# MCU.net
KiCad netlist of a schematic drawn in Altium Designer
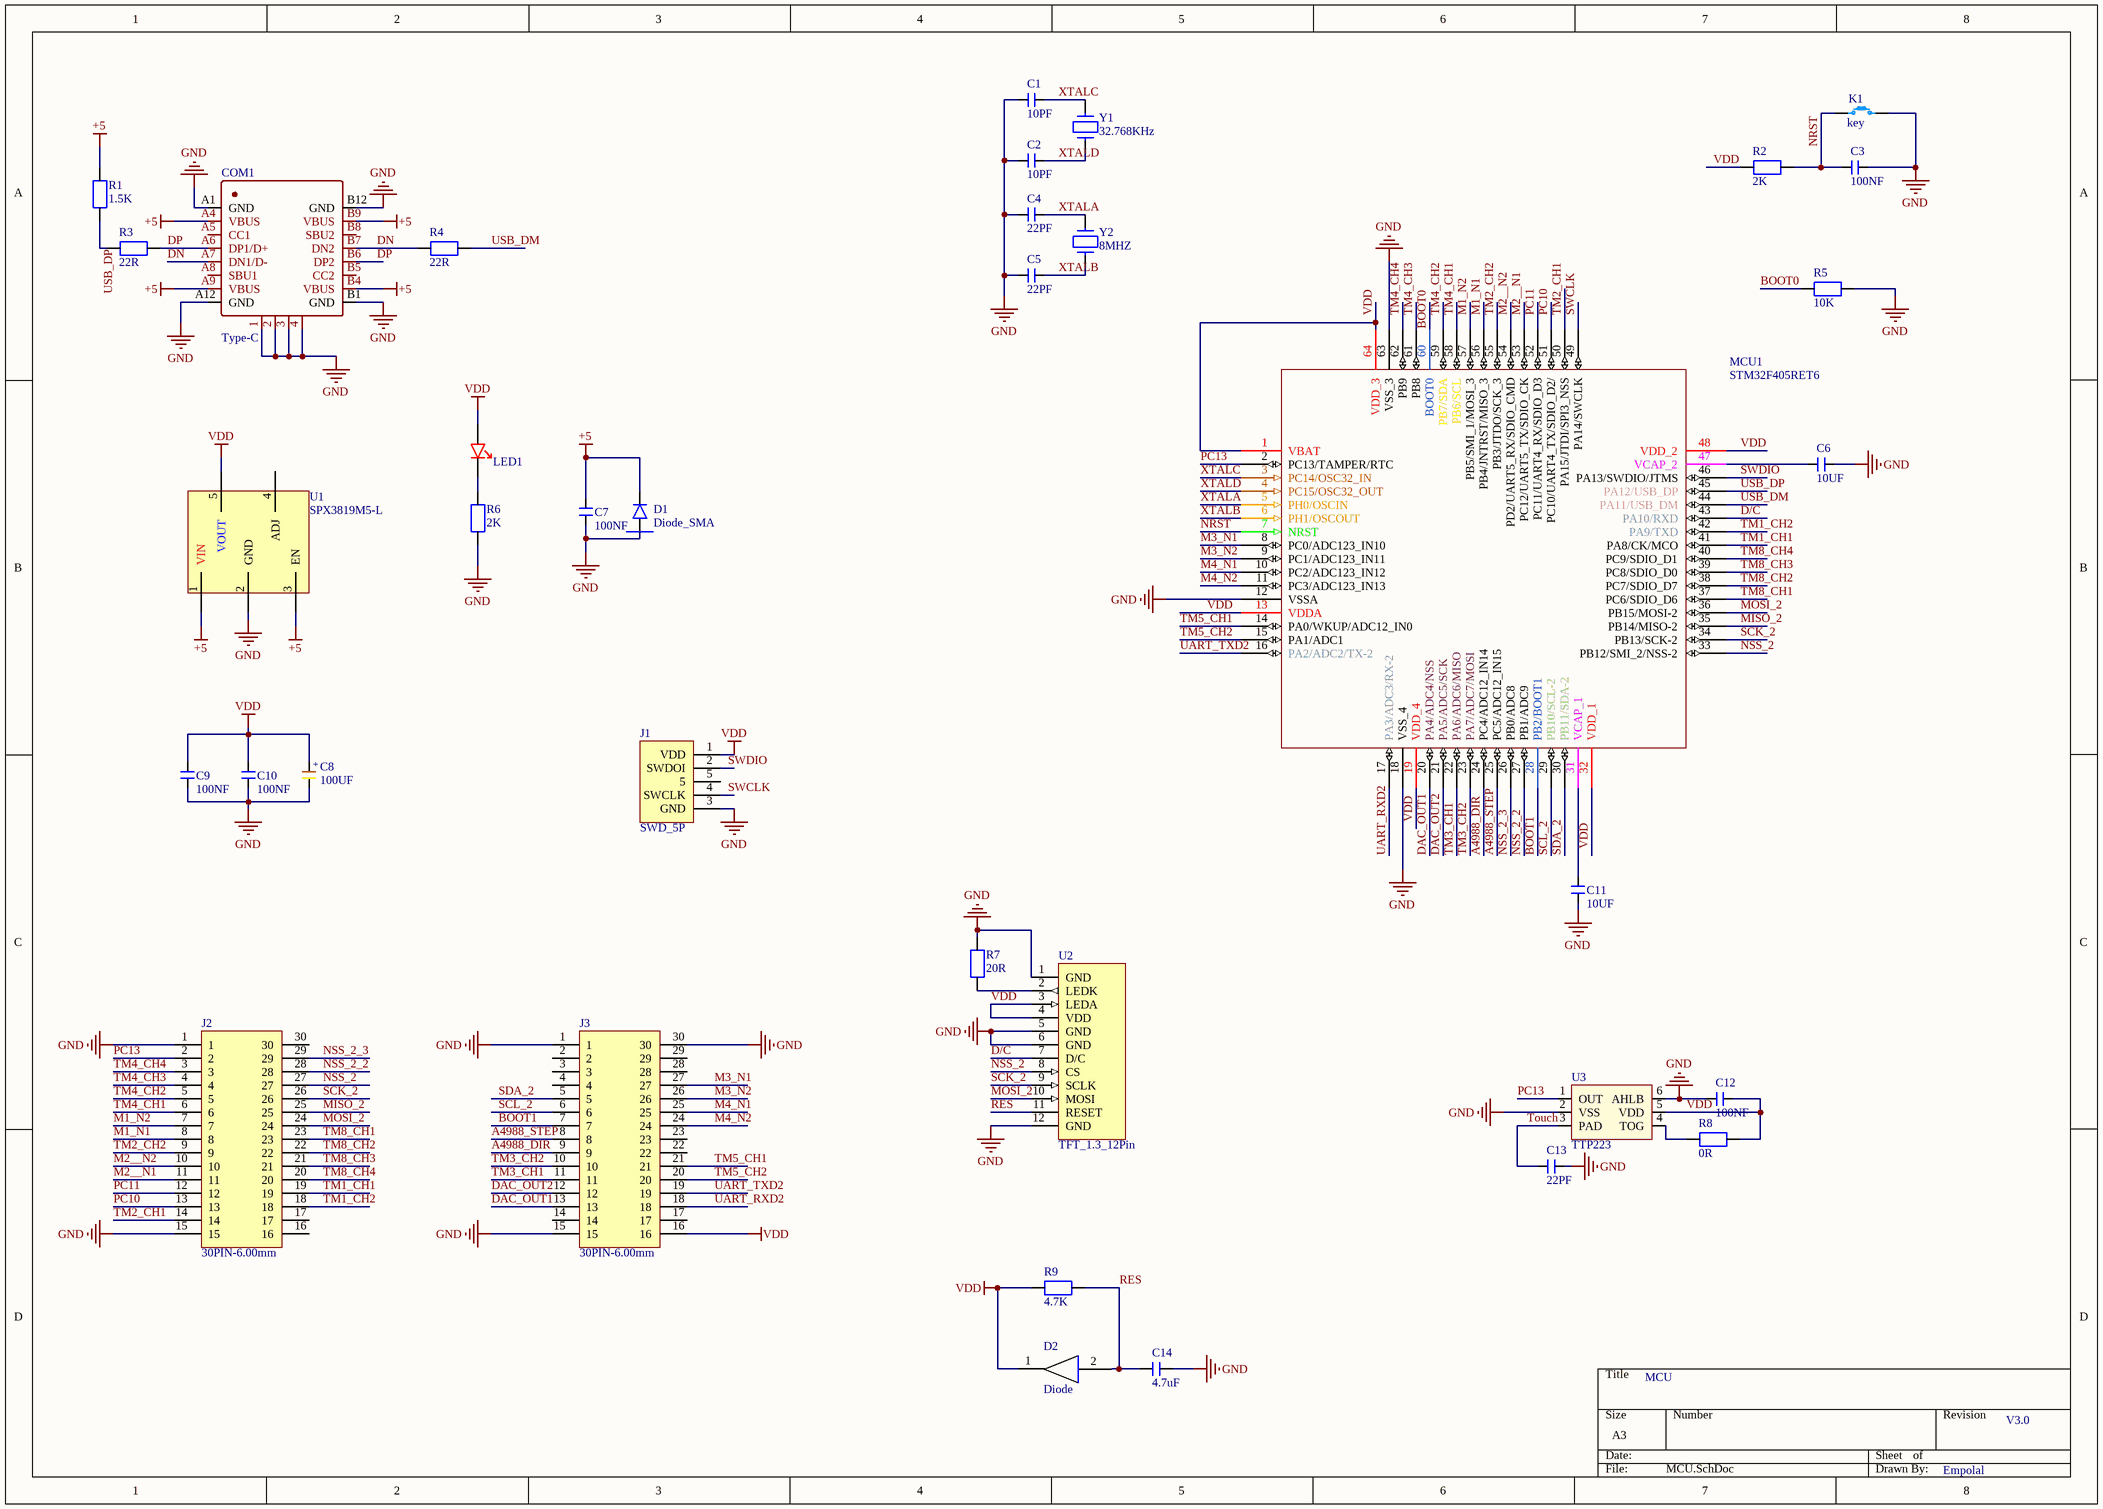
[diagram p0: MCU.SchDoc]

(export (version "E")
  (design (tool "Eeschema 10.0.6"))
  (components
    (comp (ref "C1")
      (value "10PF")
      (footprint "CAP_0603")
      (description "CAP  12~50V")
      (libsource (lib "Cavendish") (part "CAP"))
    )
    (comp (ref "C2")
      (value "10PF")
      (footprint "CAP_0603")
      (description "CAP  12~50V")
      (libsource (lib "Cavendish") (part "CAP"))
    )
    (comp (ref "C3")
      (value "100NF")
      (footprint "CAP_0603")
      (description "CAP  12~50V")
      (libsource (lib "Cavendish") (part "CAP"))
    )
    (comp (ref "C4")
      (value "22PF")
      (footprint "CAP_0603")
      (description "CAP  12~50V")
      (libsource (lib "Cavendish") (part "CAP"))
    )
    (comp (ref "C5")
      (value "22PF")
      (footprint "CAP_0603")
      (description "CAP  12~50V")
      (libsource (lib "Cavendish") (part "CAP"))
    )
    (comp (ref "C6")
      (value "10UF")
      (footprint "CAP_0603")
      (description "CAP  12~50V")
      (libsource (lib "Cavendish") (part "CAP"))
    )
    (comp (ref "C7")
      (value "100NF")
      (footprint "CAP_0603")
      (description "CAP  12~50V")
      (libsource (lib "Cavendish") (part "CAP"))
    )
    (comp (ref "C8")
      (value "100UF")
      (footprint "CAP_3528_B")
      (description "CAP  6~12V  钽电容")
      (libsource (lib "Cavendish") (part "CAP_TA"))
    )
    (comp (ref "C9")
      (value "100NF")
      (footprint "CAP_0603")
      (description "CAP  12~50V")
      (libsource (lib "Cavendish") (part "CAP"))
    )
    (comp (ref "C10")
      (value "100NF")
      (footprint "CAP_0603")
      (description "CAP  12~50V")
      (libsource (lib "Cavendish") (part "CAP"))
    )
    (comp (ref "C11")
      (value "10UF")
      (footprint "CAP_0603")
      (description "CAP  12~50V")
      (libsource (lib "Cavendish") (part "CAP"))
    )
    (comp (ref "C12")
      (value "100NF")
      (footprint "CAP_0603")
      (description "CAP  12~50V")
      (libsource (lib "Cavendish") (part "CAP"))
    )
    (comp (ref "C13")
      (value "22PF")
      (footprint "CAP_0603")
      (description "CAP  12~50V")
      (libsource (lib "Cavendish") (part "CAP"))
    )
    (comp (ref "C14")
      (value "4.7uF")
      (footprint "CAP_0603")
      (description "CAP")
      (libsource (lib "Cavendish") (part "CAP_SDM"))
    )
    (comp (ref "COM1")
      (value "Type-C")
      (footprint "USB-tYPE_C_C")
      (description "USB")
      (libsource (lib "MCU") (part "USB-type_c"))
    )
    (comp (ref "D1")
      (value "Diode_SMA")
      (footprint "DIODE_SOD123")
      (description "Diode_肖特基")
      (libsource (lib "Cavendish") (part "Diode-SM"))
    )
    (comp (ref "D2")
      (value "Diode")
      (footprint "SOD123")
      (description "开关二极管")
      (libsource (lib "Cavendish") (part "Diode-SOD"))
    )
    (comp (ref "J1")
      (value "SWD_5P")
      (footprint "XH2.54-WS-5P")
      (description "线对线连接器")
      (libsource (lib "MCU") (part "SWD_5P"))
    )
    (comp (ref "J2")
      (value "30PIN-6.00mm")
      (footprint "BTB_Double_30Pin_Up")
      (libsource (lib "Cavendish") (part "BTB_DOUBLE_30PIN"))
    )
    (comp (ref "J3")
      (value "30PIN-6.00mm")
      (footprint "BTB_Double_30Pin_Up")
      (libsource (lib "Cavendish") (part "BTB_DOUBLE_30PIN"))
    )
    (comp (ref "K1")
      (value "key")
      (footprint "KEY-A")
      (description "Key")
      (libsource (lib "Cavendish") (part "key"))
    )
    (comp (ref "LED1")
      (value "LED_R/G/B/Y")
      (footprint "RGB_3528")
      (description "LED")
      (libsource (lib "Cavendish") (part "LED"))
    )
    (comp (ref "MCU1")
      (value "STM32F405RET6")
      (footprint "LQFP_64_10X10")
      (description "MCU")
      (libsource (lib "Cavendish") (part "STM32f4_R"))
    )
    (comp (ref "R1")
      (value "1.5K")
      (footprint "RESC_0603_2")
      (description "RES 贴片")
      (libsource (lib "Cavendish") (part "RES_S"))
    )
    (comp (ref "R2")
      (value "2K")
      (footprint "RESC_0603_2")
      (description "RES 贴片")
      (libsource (lib "Cavendish") (part "RES_S"))
    )
    (comp (ref "R3")
      (value "22R")
      (footprint "RESC_0603_2")
      (description "RES 贴片")
      (libsource (lib "Cavendish") (part "RES_S"))
    )
    (comp (ref "R4")
      (value "22R")
      (footprint "RESC_0603_2")
      (description "RES 贴片")
      (libsource (lib "Cavendish") (part "RES_S"))
    )
    (comp (ref "R5")
      (value "10K")
      (footprint "RESC_0603_2")
      (description "RES 贴片")
      (libsource (lib "Cavendish") (part "RES_S"))
    )
    (comp (ref "R6")
      (value "2K")
      (footprint "RESC_0603_2")
      (description "RES 贴片")
      (libsource (lib "Cavendish") (part "RES_S"))
    )
    (comp (ref "R7")
      (value "20R")
      (footprint "RESC_0603_2")
      (description "RES 贴片")
      (libsource (lib "Cavendish") (part "RES_S"))
    )
    (comp (ref "R8")
      (value "0R")
      (footprint "RESC_0603_2")
      (description "RES 贴片")
      (libsource (lib "Cavendish") (part "RES_S"))
    )
    (comp (ref "R9")
      (value "4.7K")
      (footprint "RESC_0603_2")
      (description "RES 贴片")
      (libsource (lib "Cavendish") (part "RES_S"))
    )
    (comp (ref "U1")
      (value "SPX3819M5-L")
      (footprint "SOT23_5")
      (description "DC-DC   3.3V  500ma")
      (libsource (lib "Cavendish") (part "SPX3819M5-L"))
    )
    (comp (ref "U2")
      (value "TFT_1.3_12Pin")
      (footprint "LCD_1.3B")
      (description "ST7789V-SPI")
      (libsource (lib "Cavendish") (part "LCD_1.3   T"))
    )
    (comp (ref "U3")
      (value "TTP223")
      (footprint "SOT-23-6")
      (description "触摸芯片")
      (libsource (lib "Cavendish") (part "TTP223"))
    )
    (comp (ref "Y1")
      (value "32.768KHz")
      (footprint "XTAL_SMD_3215")
      (description "CRYSTAL")
      (libsource (lib "Cavendish") (part "XTAL"))
    )
    (comp (ref "Y2")
      (value "8MHZ")
      (footprint "XTAL_3225")
      (description "CRYSTAL")
      (libsource (lib "Cavendish") (part "XTAL"))
    )
  )
  (nets
    (net (code "1") (name "+5") (class "Default")
      (node (ref "C7") (pin "2") (pinfunction "0_2") (pintype "passive"))
      (node (ref "COM1") (pin "A4") (pinfunction "VBUS_A4") (pintype "passive"))
      (node (ref "COM1") (pin "A9") (pinfunction "VBUS_A9") (pintype "passive"))
      (node (ref "COM1") (pin "B4") (pinfunction "VBUS_B4") (pintype "passive"))
      (node (ref "COM1") (pin "B9") (pinfunction "VBUS_B9") (pintype "passive"))
      (node (ref "D1") (pin "2") (pinfunction "N_2") (pintype "passive"))
      (node (ref "R1") (pin "2") (pinfunction "2_2") (pintype "passive"))
      (node (ref "U1") (pin "1") (pinfunction "VIN_1") (pintype "passive"))
      (node (ref "U1") (pin "3") (pinfunction "EN_3") (pintype "passive"))
    )
    (net (code "2") (name "/A4988_DIR") (class "Default")
      (node (ref "J3") (pin "9") (pinfunction "9_9") (pintype "passive"))
      (node (ref "MCU1") (pin "24") (pinfunction "PC4/ADC12_IN14_24") (pintype "bidirectional"))
    )
    (net (code "3") (name "/A4988_STEP") (class "Default")
      (node (ref "J3") (pin "8") (pinfunction "8_8") (pintype "passive"))
      (node (ref "MCU1") (pin "25") (pinfunction "PC5/ADC12_IN15_25") (pintype "bidirectional"))
    )
    (net (code "4") (name "/BOOT0") (class "Default")
      (node (ref "MCU1") (pin "60") (pinfunction "BOOT0_60") (pintype "passive"))
      (node (ref "R5") (pin "1") (pinfunction "1_1") (pintype "passive"))
    )
    (net (code "5") (name "/BOOT1") (class "Default")
      (node (ref "J3") (pin "7") (pinfunction "7_7") (pintype "passive"))
      (node (ref "MCU1") (pin "28") (pinfunction "PB2/BOOT1_28") (pintype "passive"))
    )
    (net (code "6") (name "/DAC_OUT1") (class "Default")
      (node (ref "J3") (pin "13") (pinfunction "13_13") (pintype "passive"))
      (node (ref "MCU1") (pin "20") (pinfunction "PA4/ADC4/NSS_20") (pintype "bidirectional"))
    )
    (net (code "7") (name "/DAC_OUT2") (class "Default")
      (node (ref "J3") (pin "12") (pinfunction "12_12") (pintype "passive"))
      (node (ref "MCU1") (pin "21") (pinfunction "PA5/ADC5/SCK_21") (pintype "bidirectional"))
    )
    (net (code "8") (name "/DN") (class "Default")
      (node (ref "COM1") (pin "A7") (pinfunction "DN1/D-_A7") (pintype "passive"))
      (node (ref "COM1") (pin "B7") (pinfunction "DN2_B7") (pintype "passive"))
      (node (ref "R4") (pin "1") (pinfunction "1_1") (pintype "passive"))
    )
    (net (code "9") (name "/DP") (class "Default")
      (node (ref "COM1") (pin "A6") (pinfunction "DP1/D+_A6") (pintype "passive"))
      (node (ref "COM1") (pin "B6") (pinfunction "DP2_B6") (pintype "passive"))
      (node (ref "R3") (pin "2") (pinfunction "2_2") (pintype "passive"))
    )
    (net (code "10") (name "/D{slash}C") (class "Default")
      (node (ref "MCU1") (pin "43") (pinfunction "PA10/RXD_43") (pintype "bidirectional"))
      (node (ref "U2") (pin "7") (pinfunction "D/C_7") (pintype "passive"))
    )
    (net (code "11") (name "/M1_N1") (class "Default")
      (node (ref "J2") (pin "8") (pinfunction "8_8") (pintype "passive"))
      (node (ref "MCU1") (pin "56") (pinfunction "PB4/JNTRST/MISO_3_56") (pintype "bidirectional"))
    )
    (net (code "12") (name "/M1_N2") (class "Default")
      (node (ref "J2") (pin "7") (pinfunction "7_7") (pintype "passive"))
      (node (ref "MCU1") (pin "57") (pinfunction "PB5/SMI_1/MOSI_3_57") (pintype "bidirectional"))
    )
    (net (code "13") (name "/M2__N1") (class "Default")
      (node (ref "J2") (pin "11") (pinfunction "11_11") (pintype "passive"))
      (node (ref "MCU1") (pin "53") (pinfunction "PC12/UART5_TX/SDIO_CK_53") (pintype "bidirectional"))
    )
    (net (code "14") (name "/M2__N2") (class "Default")
      (node (ref "J2") (pin "10") (pinfunction "10_10") (pintype "passive"))
      (node (ref "MCU1") (pin "54") (pinfunction "PD2/UART5_RX/SDIO_CMD_54") (pintype "bidirectional"))
    )
    (net (code "15") (name "/M3_N1") (class "Default")
      (node (ref "J3") (pin "27") (pinfunction "27_27") (pintype "passive"))
      (node (ref "MCU1") (pin "8") (pinfunction "PC0/ADC123_IN10_8") (pintype "bidirectional"))
    )
    (net (code "16") (name "/M3_N2") (class "Default")
      (node (ref "J3") (pin "26") (pinfunction "26_26") (pintype "passive"))
      (node (ref "MCU1") (pin "9") (pinfunction "PC1/ADC123_IN11_9") (pintype "bidirectional"))
    )
    (net (code "17") (name "/M4_N1") (class "Default")
      (node (ref "J3") (pin "25") (pinfunction "25_25") (pintype "passive"))
      (node (ref "MCU1") (pin "10") (pinfunction "PC2/ADC123_IN12_10") (pintype "bidirectional"))
    )
    (net (code "18") (name "/M4_N2") (class "Default")
      (node (ref "J3") (pin "24") (pinfunction "24_24") (pintype "passive"))
      (node (ref "MCU1") (pin "11") (pinfunction "PC3/ADC123_IN13_11") (pintype "bidirectional"))
    )
    (net (code "19") (name "/MISO_2") (class "Default")
      (node (ref "J2") (pin "25") (pinfunction "25_25") (pintype "passive"))
      (node (ref "MCU1") (pin "35") (pinfunction "PB14/MISO-2_35") (pintype "bidirectional"))
    )
    (net (code "20") (name "/MOSI_2") (class "Default")
      (node (ref "J2") (pin "24") (pinfunction "24_24") (pintype "passive"))
      (node (ref "MCU1") (pin "36") (pinfunction "PB15/MOSI-2_36") (pintype "bidirectional"))
      (node (ref "U2") (pin "10") (pinfunction "MOSI_10") (pintype "input"))
    )
    (net (code "21") (name "/NRST") (class "Default")
      (node (ref "C3") (pin "1") (pinfunction "0_1") (pintype "passive"))
      (node (ref "K1") (pin "2") (pintype "passive"))
      (node (ref "MCU1") (pin "7") (pinfunction "NRST_7") (pintype "input"))
      (node (ref "R2") (pin "2") (pinfunction "2_2") (pintype "passive"))
    )
    (net (code "22") (name "/NSS_2") (class "Default")
      (node (ref "J2") (pin "27") (pinfunction "27_27") (pintype "passive"))
      (node (ref "MCU1") (pin "33") (pinfunction "PB12/SMI_2/NSS-2_33") (pintype "bidirectional"))
      (node (ref "U2") (pin "8") (pinfunction "CS_8") (pintype "input"))
    )
    (net (code "23") (name "/NSS_2_2") (class "Default")
      (node (ref "J2") (pin "28") (pinfunction "28_28") (pintype "passive"))
      (node (ref "MCU1") (pin "27") (pinfunction "PB1/ADC9_27") (pintype "bidirectional"))
    )
    (net (code "24") (name "/NSS_2_3") (class "Default")
      (node (ref "J2") (pin "29") (pinfunction "29_29") (pintype "passive"))
      (node (ref "MCU1") (pin "26") (pinfunction "PB0/ADC8_26") (pintype "bidirectional"))
    )
    (net (code "25") (name "/PC10") (class "Default")
      (node (ref "J2") (pin "13") (pinfunction "13_13") (pintype "passive"))
      (node (ref "MCU1") (pin "51") (pinfunction "PC10/UART4_TX/SDIO_D2/_51") (pintype "bidirectional"))
    )
    (net (code "26") (name "/PC11") (class "Default")
      (node (ref "J2") (pin "12") (pinfunction "12_12") (pintype "passive"))
      (node (ref "MCU1") (pin "52") (pinfunction "PC11/UART4_RX/SDIO_D3_52") (pintype "bidirectional"))
    )
    (net (code "27") (name "/PC13") (class "Default")
      (node (ref "J2") (pin "2") (pinfunction "2_2") (pintype "passive"))
      (node (ref "MCU1") (pin "2") (pinfunction "PC13/TAMPER/RTC_2") (pintype "bidirectional"))
      (node (ref "U3") (pin "1") (pinfunction "OUT_1") (pintype "passive"))
    )
    (net (code "28") (name "/RES") (class "Default")
      (node (ref "C14") (pin "1") (pinfunction "0_1") (pintype "passive"))
      (node (ref "D2") (pin "2") (pinfunction "P_2") (pintype "passive"))
      (node (ref "R9") (pin "2") (pinfunction "2_2") (pintype "passive"))
      (node (ref "U2") (pin "11") (pinfunction "RESET_11") (pintype "passive"))
    )
    (net (code "29") (name "/SCK_2") (class "Default")
      (node (ref "J2") (pin "26") (pinfunction "26_26") (pintype "passive"))
      (node (ref "MCU1") (pin "34") (pinfunction "PB13/SCK-2_34") (pintype "bidirectional"))
      (node (ref "U2") (pin "9") (pinfunction "SCLK_9") (pintype "input"))
    )
    (net (code "30") (name "/SCL_2") (class "Default")
      (node (ref "J3") (pin "6") (pinfunction "6_6") (pintype "passive"))
      (node (ref "MCU1") (pin "29") (pinfunction "PB10/SCL-2_29") (pintype "bidirectional"))
    )
    (net (code "31") (name "/SDA_2") (class "Default")
      (node (ref "J3") (pin "5") (pinfunction "5_5") (pintype "passive"))
      (node (ref "MCU1") (pin "30") (pinfunction "PB11/SDA-2_30") (pintype "bidirectional"))
    )
    (net (code "32") (name "/SWCLK") (class "Default")
      (node (ref "J1") (pin "4") (pinfunction "SWCLK_4") (pintype "passive"))
      (node (ref "MCU1") (pin "49") (pinfunction "PA14/SWCLK_49") (pintype "bidirectional"))
    )
    (net (code "33") (name "/SWDIO") (class "Default")
      (node (ref "J1") (pin "2") (pinfunction "SWDOI_2") (pintype "passive"))
      (node (ref "MCU1") (pin "46") (pinfunction "PA13/SWDIO/JTMS_46") (pintype "bidirectional"))
    )
    (net (code "34") (name "/TM1_CH1") (class "Default")
      (node (ref "J2") (pin "19") (pinfunction "19_19") (pintype "passive"))
      (node (ref "MCU1") (pin "41") (pinfunction "PA8/CK/MCO_41") (pintype "bidirectional"))
    )
    (net (code "35") (name "/TM1_CH2") (class "Default")
      (node (ref "J2") (pin "18") (pinfunction "18_18") (pintype "passive"))
      (node (ref "MCU1") (pin "42") (pinfunction "PA9/TXD_42") (pintype "bidirectional"))
    )
    (net (code "36") (name "/TM2_CH1") (class "Default")
      (node (ref "J2") (pin "14") (pinfunction "14_14") (pintype "passive"))
      (node (ref "MCU1") (pin "50") (pinfunction "PA15/JTDI/SPI3_NSS_50") (pintype "bidirectional"))
    )
    (net (code "37") (name "/TM2_CH2") (class "Default")
      (node (ref "J2") (pin "9") (pinfunction "9_9") (pintype "passive"))
      (node (ref "MCU1") (pin "55") (pinfunction "PB3/JTDO/SCK_3_55") (pintype "bidirectional"))
    )
    (net (code "38") (name "/TM3_CH1") (class "Default")
      (node (ref "J3") (pin "11") (pinfunction "11_11") (pintype "passive"))
      (node (ref "MCU1") (pin "22") (pinfunction "PA6/ADC6/MISO_22") (pintype "bidirectional"))
    )
    (net (code "39") (name "/TM3_CH2") (class "Default")
      (node (ref "J3") (pin "10") (pinfunction "10_10") (pintype "passive"))
      (node (ref "MCU1") (pin "23") (pinfunction "PA7/ADC7/MOSI_23") (pintype "bidirectional"))
    )
    (net (code "40") (name "/TM4_CH1") (class "Default")
      (node (ref "J2") (pin "6") (pinfunction "6_6") (pintype "passive"))
      (node (ref "MCU1") (pin "58") (pinfunction "PB6/SCL_58") (pintype "bidirectional"))
    )
    (net (code "41") (name "/TM4_CH2") (class "Default")
      (node (ref "J2") (pin "5") (pinfunction "5_5") (pintype "passive"))
      (node (ref "MCU1") (pin "59") (pinfunction "PB7/SDA_59") (pintype "bidirectional"))
    )
    (net (code "42") (name "/TM4_CH3") (class "Default")
      (node (ref "J2") (pin "4") (pinfunction "4_4") (pintype "passive"))
      (node (ref "MCU1") (pin "61") (pinfunction "PB8_61") (pintype "bidirectional"))
    )
    (net (code "43") (name "/TM4_CH4") (class "Default")
      (node (ref "J2") (pin "3") (pinfunction "3_3") (pintype "passive"))
      (node (ref "MCU1") (pin "62") (pinfunction "PB9_62") (pintype "bidirectional"))
    )
    (net (code "44") (name "/TM5_CH1") (class "Default")
      (node (ref "J3") (pin "21") (pinfunction "21_21") (pintype "passive"))
      (node (ref "MCU1") (pin "14") (pinfunction "PA0/WKUP/ADC12_IN0_14") (pintype "bidirectional"))
    )
    (net (code "45") (name "/TM5_CH2") (class "Default")
      (node (ref "J3") (pin "20") (pinfunction "20_20") (pintype "passive"))
      (node (ref "MCU1") (pin "15") (pinfunction "PA1/ADC1_15") (pintype "bidirectional"))
    )
    (net (code "46") (name "/TM8_CH1") (class "Default")
      (node (ref "J2") (pin "23") (pinfunction "23_23") (pintype "passive"))
      (node (ref "MCU1") (pin "37") (pinfunction "PC6/SDIO_D6_37") (pintype "bidirectional"))
    )
    (net (code "47") (name "/TM8_CH2") (class "Default")
      (node (ref "J2") (pin "22") (pinfunction "22_22") (pintype "passive"))
      (node (ref "MCU1") (pin "38") (pinfunction "PC7/SDIO_D7_38") (pintype "bidirectional"))
    )
    (net (code "48") (name "/TM8_CH3") (class "Default")
      (node (ref "J2") (pin "21") (pinfunction "21_21") (pintype "passive"))
      (node (ref "MCU1") (pin "39") (pinfunction "PC8/SDIO_D0_39") (pintype "bidirectional"))
    )
    (net (code "49") (name "/TM8_CH4") (class "Default")
      (node (ref "J2") (pin "20") (pinfunction "20_20") (pintype "passive"))
      (node (ref "MCU1") (pin "40") (pinfunction "PC9/SDIO_D1_40") (pintype "bidirectional"))
    )
    (net (code "50") (name "/Touch") (class "Default")
      (node (ref "C13") (pin "1") (pinfunction "0_1") (pintype "passive"))
      (node (ref "U3") (pin "3") (pinfunction "PAD_3") (pintype "passive"))
    )
    (net (code "51") (name "/UART_RXD2") (class "Default")
      (node (ref "J3") (pin "18") (pinfunction "18_18") (pintype "passive"))
      (node (ref "MCU1") (pin "17") (pinfunction "PA3/ADC3/RX-2_17") (pintype "bidirectional"))
    )
    (net (code "52") (name "/UART_TXD2") (class "Default")
      (node (ref "J3") (pin "19") (pinfunction "19_19") (pintype "passive"))
      (node (ref "MCU1") (pin "16") (pinfunction "PA2/ADC2/TX-2_16") (pintype "bidirectional"))
    )
    (net (code "53") (name "/USB_DM") (class "Default")
      (node (ref "MCU1") (pin "44") (pinfunction "PA11/USB_DM_44") (pintype "bidirectional"))
      (node (ref "R4") (pin "2") (pinfunction "2_2") (pintype "passive"))
    )
    (net (code "54") (name "/USB_DP") (class "Default")
      (node (ref "MCU1") (pin "45") (pinfunction "PA12/USB_DP_45") (pintype "bidirectional"))
      (node (ref "R1") (pin "1") (pinfunction "1_1") (pintype "passive"))
      (node (ref "R3") (pin "1") (pinfunction "1_1") (pintype "passive"))
    )
    (net (code "55") (name "/XTALA") (class "Default")
      (node (ref "C4") (pin "2") (pinfunction "0_2") (pintype "passive"))
      (node (ref "MCU1") (pin "5") (pinfunction "PH0/OSCIN_5") (pintype "input"))
      (node (ref "Y2") (pin "2") (pinfunction "2_2") (pintype "passive"))
    )
    (net (code "56") (name "/XTALB") (class "Default")
      (node (ref "C5") (pin "2") (pinfunction "0_2") (pintype "passive"))
      (node (ref "MCU1") (pin "6") (pinfunction "PH1/OSCOUT_6") (pintype "input"))
      (node (ref "Y2") (pin "1") (pinfunction "1_1") (pintype "passive"))
    )
    (net (code "57") (name "/XTALC") (class "Default")
      (node (ref "C1") (pin "2") (pinfunction "0_2") (pintype "passive"))
      (node (ref "MCU1") (pin "3") (pinfunction "PC14/OSC32_IN_3") (pintype "input"))
      (node (ref "Y1") (pin "2") (pinfunction "2_2") (pintype "passive"))
    )
    (net (code "58") (name "/XTALD") (class "Default")
      (node (ref "C2") (pin "2") (pinfunction "0_2") (pintype "passive"))
      (node (ref "MCU1") (pin "4") (pinfunction "PC15/OSC32_OUT_4") (pintype "input"))
      (node (ref "Y1") (pin "1") (pinfunction "1_1") (pintype "passive"))
    )
    (net (code "59") (name "GND") (class "Default")
      (node (ref "C1") (pin "1") (pinfunction "0_1") (pintype "passive"))
      (node (ref "C10") (pin "1") (pinfunction "0_1") (pintype "passive"))
      (node (ref "C11") (pin "1") (pinfunction "0_1") (pintype "passive"))
      (node (ref "C12") (pin "1") (pinfunction "0_1") (pintype "passive"))
      (node (ref "C13") (pin "2") (pinfunction "0_2") (pintype "passive"))
      (node (ref "C14") (pin "2") (pinfunction "0_2") (pintype "passive"))
      (node (ref "C2") (pin "1") (pinfunction "0_1") (pintype "passive"))
      (node (ref "C3") (pin "2") (pinfunction "0_2") (pintype "passive"))
      (node (ref "C4") (pin "1") (pinfunction "0_1") (pintype "passive"))
      (node (ref "C5") (pin "1") (pinfunction "0_1") (pintype "passive"))
      (node (ref "C6") (pin "2") (pinfunction "0_2") (pintype "passive"))
      (node (ref "C7") (pin "1") (pinfunction "0_1") (pintype "passive"))
      (node (ref "C8") (pin "2") (pinfunction "0_2") (pintype "passive"))
      (node (ref "C9") (pin "1") (pinfunction "0_1") (pintype "passive"))
      (node (ref "COM1") (pin "1") (pinfunction "1_1") (pintype "passive"))
      (node (ref "COM1") (pin "2") (pinfunction "2_2") (pintype "passive"))
      (node (ref "COM1") (pin "3") (pinfunction "3_3") (pintype "passive"))
      (node (ref "COM1") (pin "4") (pinfunction "4_4") (pintype "passive"))
      (node (ref "COM1") (pin "A1") (pinfunction "GND_A1") (pintype "passive"))
      (node (ref "COM1") (pin "A12") (pinfunction "GND_A12") (pintype "passive"))
      (node (ref "COM1") (pin "B1") (pinfunction "GND_B1") (pintype "passive"))
      (node (ref "COM1") (pin "B12") (pinfunction "GND_B12") (pintype "passive"))
      (node (ref "D1") (pin "1") (pinfunction "P_1") (pintype "passive"))
      (node (ref "J1") (pin "3") (pinfunction "GND_3") (pintype "passive"))
      (node (ref "J2") (pin "1") (pinfunction "1_1") (pintype "passive"))
      (node (ref "J2") (pin "15") (pinfunction "15_15") (pintype "passive"))
      (node (ref "J3") (pin "1") (pinfunction "1_1") (pintype "passive"))
      (node (ref "J3") (pin "15") (pinfunction "15_15") (pintype "passive"))
      (node (ref "J3") (pin "30") (pinfunction "30_30") (pintype "passive"))
      (node (ref "K1") (pin "1") (pintype "passive"))
      (node (ref "MCU1") (pin "12") (pinfunction "VSSA_12") (pintype "power_in"))
      (node (ref "MCU1") (pin "18") (pinfunction "VSS_4_18") (pintype "power_in"))
      (node (ref "MCU1") (pin "63") (pinfunction "VSS_3_63") (pintype "power_in"))
      (node (ref "R5") (pin "2") (pinfunction "2_2") (pintype "passive"))
      (node (ref "R6") (pin "1") (pinfunction "1_1") (pintype "passive"))
      (node (ref "R7") (pin "2") (pinfunction "2_2") (pintype "passive"))
      (node (ref "U1") (pin "2") (pinfunction "GND_2") (pintype "passive"))
      (node (ref "U2") (pin "1") (pinfunction "GND_1") (pintype "passive"))
      (node (ref "U2") (pin "12") (pinfunction "GND_12") (pintype "passive"))
      (node (ref "U2") (pin "5") (pinfunction "GND_5") (pintype "passive"))
      (node (ref "U2") (pin "6") (pinfunction "GND_6") (pintype "passive"))
      (node (ref "U3") (pin "2") (pinfunction "VSS_2") (pintype "passive"))
      (node (ref "U3") (pin "6") (pinfunction "AHLB_6") (pintype "passive"))
    )
    (net (code "60") (name "Net-(LED1--)") (class "Default")
      (node (ref "LED1") (pin "1") (pinfunction "-_1") (pintype "passive"))
      (node (ref "R6") (pin "2") (pinfunction "2_2") (pintype "passive"))
    )
    (net (code "61") (name "Net-(MCU1-VCAP_1)") (class "Default")
      (node (ref "C11") (pin "2") (pinfunction "0_2") (pintype "passive"))
      (node (ref "MCU1") (pin "31") (pinfunction "VCAP_1_31") (pintype "passive"))
    )
    (net (code "62") (name "Net-(MCU1-VCAP_2)") (class "Default")
      (node (ref "C6") (pin "1") (pinfunction "0_1") (pintype "passive"))
      (node (ref "MCU1") (pin "47") (pinfunction "VCAP_2_47") (pintype "passive"))
    )
    (net (code "63") (name "Net-(U2-LEDK)") (class "Default")
      (node (ref "R7") (pin "1") (pinfunction "1_1") (pintype "passive"))
      (node (ref "U2") (pin "2") (pinfunction "LEDK_2") (pintype "output"))
    )
    (net (code "64") (name "Net-(U3-TOG)") (class "Default")
      (node (ref "R8") (pin "2") (pinfunction "2_2") (pintype "passive"))
      (node (ref "U3") (pin "4") (pinfunction "TOG_4") (pintype "passive"))
    )
    (net (code "65") (name "VDD") (class "Default")
      (node (ref "C10") (pin "2") (pinfunction "0_2") (pintype "passive"))
      (node (ref "C12") (pin "2") (pinfunction "0_2") (pintype "passive"))
      (node (ref "C8") (pin "1") (pinfunction "0_1") (pintype "passive"))
      (node (ref "C9") (pin "2") (pinfunction "0_2") (pintype "passive"))
      (node (ref "D2") (pin "1") (pinfunction "N_1") (pintype "passive"))
      (node (ref "J1") (pin "1") (pinfunction "VDD_1") (pintype "passive"))
      (node (ref "J3") (pin "16") (pinfunction "16_16") (pintype "passive"))
      (node (ref "LED1") (pin "2") (pinfunction "+_2") (pintype "passive"))
      (node (ref "MCU1") (pin "1") (pinfunction "VBAT_1") (pintype "power_in"))
      (node (ref "MCU1") (pin "13") (pinfunction "VDDA_13") (pintype "power_in"))
      (node (ref "MCU1") (pin "19") (pinfunction "VDD_4_19") (pintype "power_in"))
      (node (ref "MCU1") (pin "32") (pinfunction "VDD_1_32") (pintype "power_in"))
      (node (ref "MCU1") (pin "48") (pinfunction "VDD_2_48") (pintype "power_in"))
      (node (ref "MCU1") (pin "64") (pinfunction "VDD_3_64") (pintype "power_in"))
      (node (ref "R2") (pin "1") (pinfunction "1_1") (pintype "passive"))
      (node (ref "R8") (pin "1") (pinfunction "1_1") (pintype "passive"))
      (node (ref "R9") (pin "1") (pinfunction "1_1") (pintype "passive"))
      (node (ref "U1") (pin "5") (pinfunction "VOUT_5") (pintype "passive"))
      (node (ref "U2") (pin "3") (pinfunction "LEDA_3") (pintype "input"))
      (node (ref "U2") (pin "4") (pinfunction "VDD_4") (pintype "passive"))
      (node (ref "U3") (pin "5") (pinfunction "VDD_5") (pintype "passive"))
    )
    (net (code "66") (name "unconnected-(COM1-CC1-PadA5)") (class "Default")
      (node (ref "COM1") (pin "A5") (pinfunction "CC1_A5") (pintype "passive"))
    )
    (net (code "67") (name "unconnected-(COM1-CC2-PadB5)") (class "Default")
      (node (ref "COM1") (pin "B5") (pinfunction "CC2_B5") (pintype "passive"))
    )
    (net (code "68") (name "unconnected-(COM1-SBU1-PadA8)") (class "Default")
      (node (ref "COM1") (pin "A8") (pinfunction "SBU1_A8") (pintype "passive"))
    )
    (net (code "69") (name "unconnected-(COM1-SBU2-PadB8)") (class "Default")
      (node (ref "COM1") (pin "B8") (pinfunction "SBU2_B8") (pintype "passive"))
    )
    (net (code "70") (name "unconnected-(J1-Pad5)") (class "Default")
      (node (ref "J1") (pin "5") (pinfunction "5_5") (pintype "passive"))
    )
    (net (code "71") (name "unconnected-(J2-Pad16)") (class "Default")
      (node (ref "J2") (pin "16") (pinfunction "16_16") (pintype "passive"))
    )
    (net (code "72") (name "unconnected-(J2-Pad17)") (class "Default")
      (node (ref "J2") (pin "17") (pinfunction "17_17") (pintype "passive"))
    )
    (net (code "73") (name "unconnected-(J2-Pad30)") (class "Default")
      (node (ref "J2") (pin "30") (pinfunction "30_30") (pintype "passive"))
    )
    (net (code "74") (name "unconnected-(J3-Pad2)") (class "Default")
      (node (ref "J3") (pin "2") (pinfunction "2_2") (pintype "passive"))
    )
    (net (code "75") (name "unconnected-(J3-Pad3)") (class "Default")
      (node (ref "J3") (pin "3") (pinfunction "3_3") (pintype "passive"))
    )
    (net (code "76") (name "unconnected-(J3-Pad4)") (class "Default")
      (node (ref "J3") (pin "4") (pinfunction "4_4") (pintype "passive"))
    )
    (net (code "77") (name "unconnected-(J3-Pad14)") (class "Default")
      (node (ref "J3") (pin "14") (pinfunction "14_14") (pintype "passive"))
    )
    (net (code "78") (name "unconnected-(J3-Pad17)") (class "Default")
      (node (ref "J3") (pin "17") (pinfunction "17_17") (pintype "passive"))
    )
    (net (code "79") (name "unconnected-(J3-Pad22)") (class "Default")
      (node (ref "J3") (pin "22") (pinfunction "22_22") (pintype "passive"))
    )
    (net (code "80") (name "unconnected-(J3-Pad23)") (class "Default")
      (node (ref "J3") (pin "23") (pinfunction "23_23") (pintype "passive"))
    )
    (net (code "81") (name "unconnected-(J3-Pad28)") (class "Default")
      (node (ref "J3") (pin "28") (pinfunction "28_28") (pintype "passive"))
    )
    (net (code "82") (name "unconnected-(J3-Pad29)") (class "Default")
      (node (ref "J3") (pin "29") (pinfunction "29_29") (pintype "passive"))
    )
    (net (code "83") (name "unconnected-(U1-ADJ-Pad4)") (class "Default")
      (node (ref "U1") (pin "4") (pinfunction "ADJ_4") (pintype "passive"))
    )
  )
)
